# m328.net
KiCad netlist of a schematic drawn in EAGLE
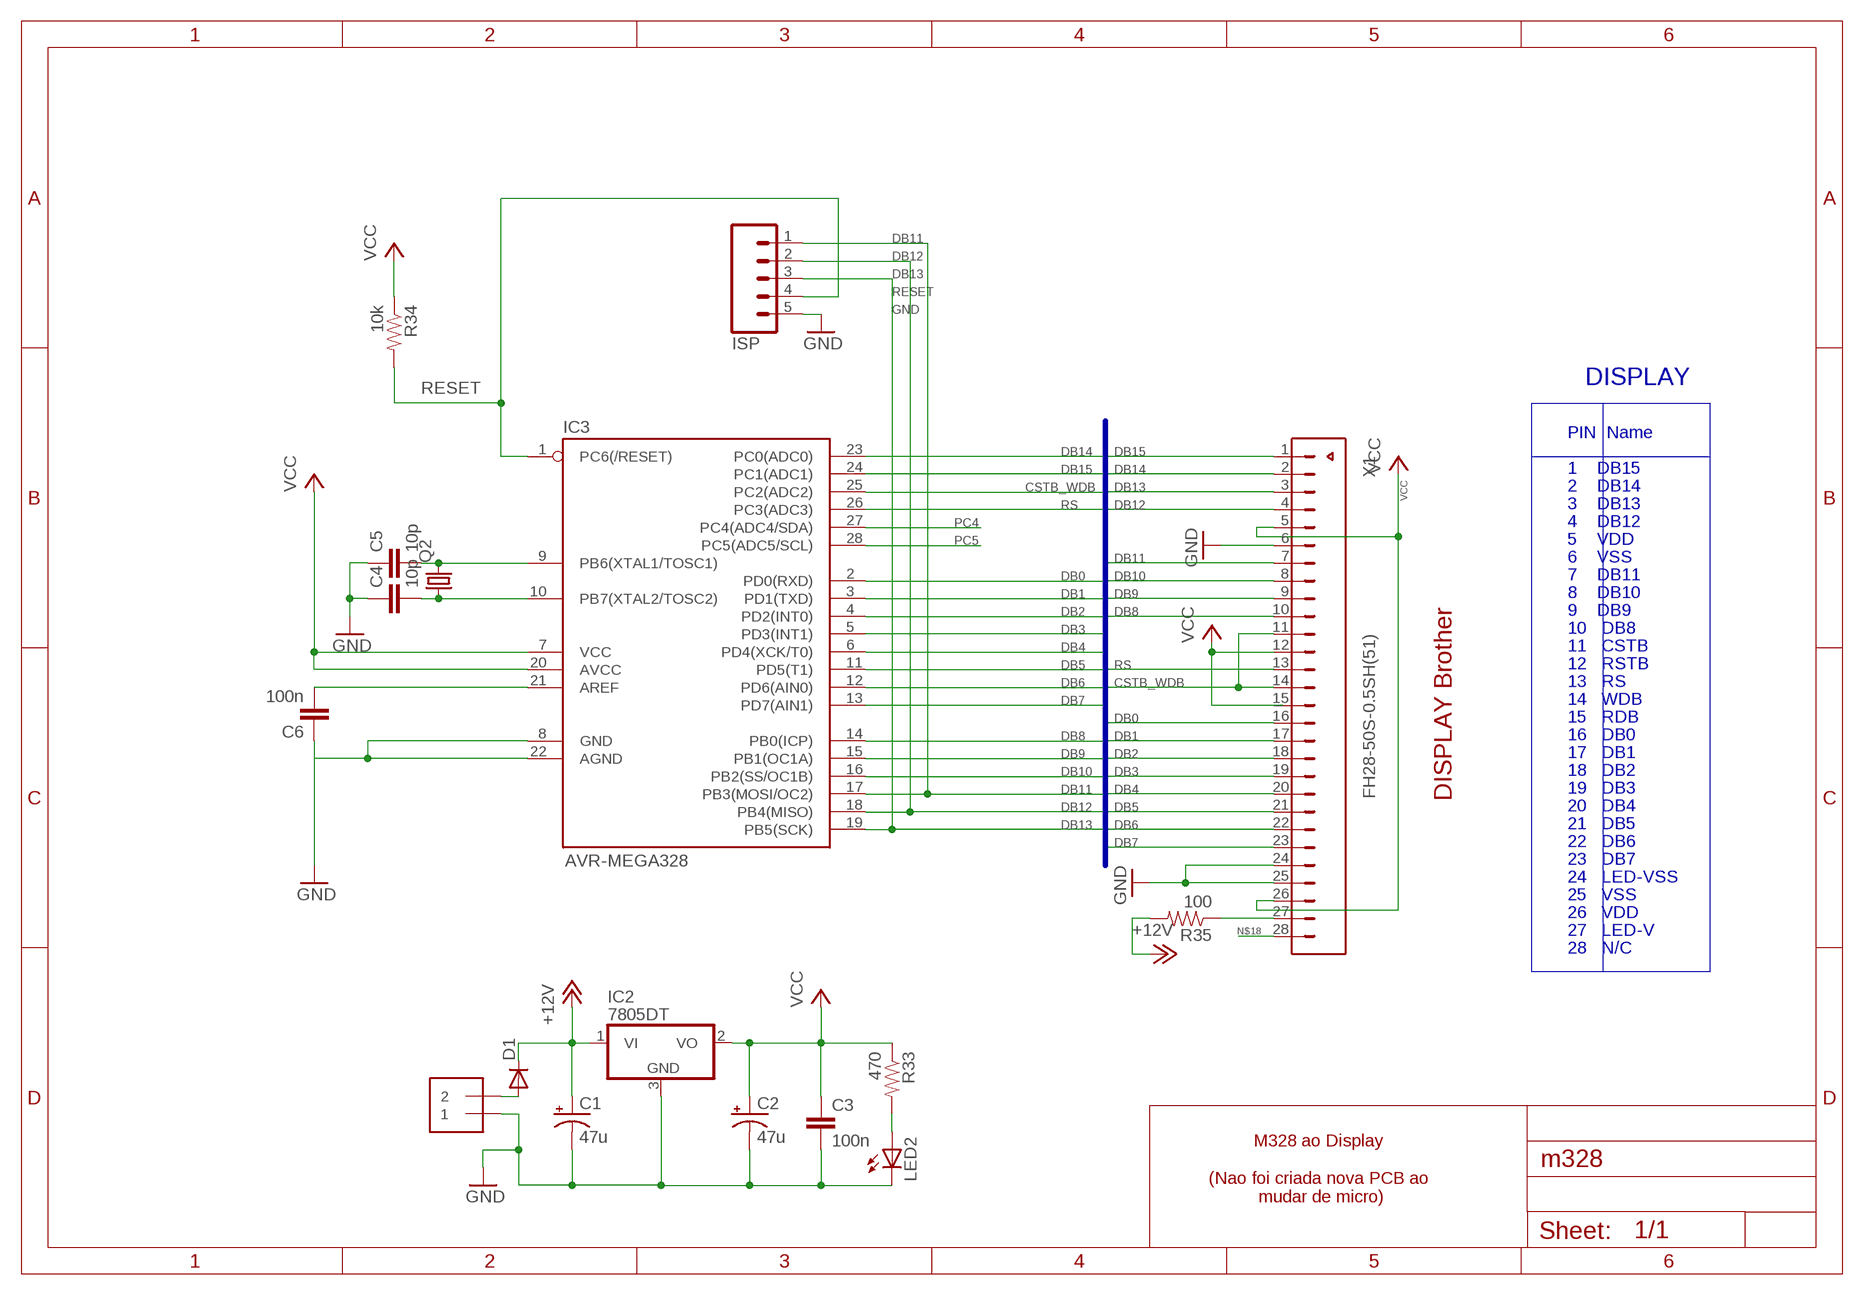
[diagram p0: schematic, sheet 1]

(export (version "E")
  (design (tool "Eeschema 10.0.6"))
  (components
    (comp (ref "C1")
      (value "47u")
      (footprint "eagle-import:EIA3216-KIT")
      (libsource (lib "eagle-import") (part "CAP_POL1206-KIT"))
    )
    (comp (ref "C2")
      (value "47u")
      (footprint "eagle-import:EIA3216-KIT")
      (libsource (lib "eagle-import") (part "CAP_POL1206-KIT"))
    )
    (comp (ref "C3")
      (value "100n")
      (footprint "eagle-import:0805")
      (libsource (lib "eagle-import") (part "CAP0805"))
    )
    (comp (ref "C4")
      (value "10p")
      (footprint "eagle-import:0805")
      (libsource (lib "eagle-import") (part "CAP0805"))
    )
    (comp (ref "C5")
      (value "10p")
      (footprint "eagle-import:0805")
      (libsource (lib "eagle-import") (part "CAP0805"))
    )
    (comp (ref "C6")
      (value "100n")
      (footprint "eagle-import:0805")
      (libsource (lib "eagle-import") (part "CAP0805"))
    )
    (comp (ref "D1")
      (value "DIODESMA-KIT")
      (footprint "eagle-import:SMA-DIODE-KIT")
      (libsource (lib "eagle-import") (part "DIODESMA-KIT"))
    )
    (comp (ref "IC2")
      (value "7805DT")
      (footprint "eagle-import:TO252")
      (libsource (lib "eagle-import") (part "78DT05"))
    )
    (comp (ref "IC3")
      (value "AVR-MEGA328")
      (footprint "eagle-import:DIL28-3")
      (libsource (lib "eagle-import") (part "AVR-MEGA8-PPTH"))
    )
    (comp (ref "ISP")
      (value "M05PTH_LONGPADS")
      (footprint "eagle-import:1X05_LONGPADS")
      (libsource (lib "eagle-import") (part "M05PTH_LONGPADS"))
    )
    (comp (ref "J2")
      (value "1X2-3.5MM")
      (footprint "eagle-import:1X2-3.5MM")
      (libsource (lib "eagle-import") (part "1X2-3.5MM"))
    )
    (comp (ref "LED2")
      (value "LED3MM")
      (footprint "eagle-import:LED3MM")
      (libsource (lib "eagle-import") (part "LED3MM"))
    )
    (comp (ref "Q2")
      (value "CRYSTALHC49UP")
      (footprint "eagle-import:HC49UP")
      (fields (field (name "OC_FARNELL") "unknown"))
      (libsource (lib "eagle-import") (part "CRYSTALHC49UP"))
    )
    (comp (ref "R33")
      (value "470")
      (footprint "eagle-import:0805")
      (libsource (lib "eagle-import") (part "RESISTOR0805-RES"))
    )
    (comp (ref "R34")
      (value "10k")
      (footprint "eagle-import:0805")
      (libsource (lib "eagle-import") (part "RESISTOR0805-RES"))
    )
    (comp (ref "R35")
      (value "100")
      (footprint "eagle-import:0805")
      (libsource (lib "eagle-import") (part "RESISTOR0805-RES"))
    )
    (comp (ref "X1")
      (value "FH28-50S-0.5SH(51)")
      (footprint "eagle-import:FH28-50S-0.5SH(51)")
      (libsource (lib "eagle-import") (part "FH28-50S-0.5SH(51)"))
    )
  )
  (nets
    (net (code "2") (name "+12V") (class "Default")
      (node (ref "C1") (pin "A") (pinfunction "+_A") (pintype "passive"))
      (node (ref "D1") (pin "C") (pinfunction "C_C") (pintype "passive"))
      (node (ref "IC2") (pin "1") (pinfunction "VI_1") (pintype "input"))
      (node (ref "R35") (pin "2") (pinfunction "2_2") (pintype "passive"))
    )
    (net (code "3") (name "/CSTB_WDB") (class "Default")
      (node (ref "IC3") (pin "25") (pinfunction "PC2(ADC2)_25") (pintype "bidirectional"))
      (node (ref "X1") (pin "11") (pinfunction "11_11") (pintype "passive"))
      (node (ref "X1") (pin "14") (pinfunction "14_14") (pintype "passive"))
    )
    (net (code "4") (name "/DB0") (class "Default")
      (node (ref "IC3") (pin "2") (pinfunction "PD0(RXD)_2") (pintype "bidirectional"))
      (node (ref "X1") (pin "16") (pinfunction "16_16") (pintype "passive"))
    )
    (net (code "5") (name "/DB1") (class "Default")
      (node (ref "IC3") (pin "3") (pinfunction "PD1(TXD)_3") (pintype "bidirectional"))
      (node (ref "X1") (pin "17") (pinfunction "17_17") (pintype "passive"))
    )
    (net (code "6") (name "/DB2") (class "Default")
      (node (ref "IC3") (pin "4") (pinfunction "PD2(INT0)_4") (pintype "bidirectional"))
      (node (ref "X1") (pin "18") (pinfunction "18_18") (pintype "passive"))
    )
    (net (code "7") (name "/DB3") (class "Default")
      (node (ref "IC3") (pin "5") (pinfunction "PD3(INT1)_5") (pintype "bidirectional"))
      (node (ref "X1") (pin "19") (pinfunction "19_19") (pintype "passive"))
    )
    (net (code "8") (name "/DB4") (class "Default")
      (node (ref "IC3") (pin "6") (pinfunction "PD4(XCK/T0)_6") (pintype "bidirectional"))
      (node (ref "X1") (pin "20") (pinfunction "20_20") (pintype "passive"))
    )
    (net (code "9") (name "/DB5") (class "Default")
      (node (ref "IC3") (pin "11") (pinfunction "PD5(T1)_11") (pintype "bidirectional"))
      (node (ref "X1") (pin "21") (pinfunction "21_21") (pintype "passive"))
    )
    (net (code "10") (name "/DB6") (class "Default")
      (node (ref "IC3") (pin "12") (pinfunction "PD6(AIN0)_12") (pintype "bidirectional"))
      (node (ref "X1") (pin "22") (pinfunction "22_22") (pintype "passive"))
    )
    (net (code "11") (name "/DB7") (class "Default")
      (node (ref "IC3") (pin "13") (pinfunction "PD7(AIN1)_13") (pintype "bidirectional"))
      (node (ref "X1") (pin "23") (pinfunction "23_23") (pintype "passive"))
    )
    (net (code "12") (name "/DB8") (class "Default")
      (node (ref "IC3") (pin "14") (pinfunction "PB0(ICP)_14") (pintype "bidirectional"))
      (node (ref "X1") (pin "10") (pinfunction "10_10") (pintype "passive"))
    )
    (net (code "13") (name "/DB9") (class "Default")
      (node (ref "IC3") (pin "15") (pinfunction "PB1(OC1A)_15") (pintype "bidirectional"))
      (node (ref "X1") (pin "9") (pinfunction "9_9") (pintype "passive"))
    )
    (net (code "14") (name "/DB10") (class "Default")
      (node (ref "IC3") (pin "16") (pinfunction "PB2(SS/OC1B)_16") (pintype "bidirectional"))
      (node (ref "X1") (pin "8") (pinfunction "8_8") (pintype "passive"))
    )
    (net (code "15") (name "/DB11") (class "Default")
      (node (ref "IC3") (pin "17") (pinfunction "PB3(MOSI/OC2)_17") (pintype "bidirectional"))
      (node (ref "ISP") (pin "1") (pinfunction "1_1") (pintype "passive"))
      (node (ref "X1") (pin "7") (pinfunction "7_7") (pintype "passive"))
    )
    (net (code "16") (name "/DB12") (class "Default")
      (node (ref "IC3") (pin "18") (pinfunction "PB4(MISO)_18") (pintype "bidirectional"))
      (node (ref "ISP") (pin "2") (pinfunction "2_2") (pintype "passive"))
      (node (ref "X1") (pin "4") (pinfunction "4_4") (pintype "passive"))
    )
    (net (code "17") (name "/DB13") (class "Default")
      (node (ref "IC3") (pin "19") (pinfunction "PB5(SCK)_19") (pintype "bidirectional"))
      (node (ref "ISP") (pin "3") (pinfunction "3_3") (pintype "passive"))
      (node (ref "X1") (pin "3") (pinfunction "3_3") (pintype "passive"))
    )
    (net (code "18") (name "/DB14") (class "Default")
      (node (ref "IC3") (pin "23") (pinfunction "PC0(ADC0)_23") (pintype "bidirectional"))
      (node (ref "X1") (pin "2") (pinfunction "2_2") (pintype "passive"))
    )
    (net (code "19") (name "/DB15") (class "Default")
      (node (ref "IC3") (pin "24") (pinfunction "PC1(ADC1)_24") (pintype "bidirectional"))
      (node (ref "X1") (pin "1") (pinfunction "1_1") (pintype "passive"))
    )
    (net (code "20") (name "/N$18") (class "Default")
      (node (ref "X1") (pin "28") (pinfunction "28_28") (pintype "passive"))
    )
    (net (code "21") (name "/PC4") (class "Default")
      (node (ref "IC3") (pin "27") (pinfunction "PC4(ADC4/SDA)_27") (pintype "bidirectional"))
    )
    (net (code "22") (name "/PC5") (class "Default")
      (node (ref "IC3") (pin "28") (pinfunction "PC5(ADC5/SCL)_28") (pintype "bidirectional"))
    )
    (net (code "23") (name "/RESET") (class "Default")
      (node (ref "IC3") (pin "1") (pinfunction "PC6(/RESET)_1") (pintype "bidirectional"))
      (node (ref "ISP") (pin "4") (pinfunction "4_4") (pintype "passive"))
      (node (ref "R34") (pin "2") (pinfunction "2_2") (pintype "passive"))
    )
    (net (code "24") (name "/RS") (class "Default")
      (node (ref "IC3") (pin "26") (pinfunction "PC3(ADC3)_26") (pintype "bidirectional"))
      (node (ref "X1") (pin "13") (pinfunction "13_13") (pintype "passive"))
    )
    (net (code "26") (name "GND") (class "Default")
      (node (ref "C1") (pin "C") (pinfunction "-_C") (pintype "passive"))
      (node (ref "C2") (pin "C") (pinfunction "-_C") (pintype "passive"))
      (node (ref "C3") (pin "2") (pinfunction "2_2") (pintype "passive"))
      (node (ref "C4") (pin "1") (pinfunction "1_1") (pintype "passive"))
      (node (ref "C5") (pin "1") (pinfunction "1_1") (pintype "passive"))
      (node (ref "C6") (pin "1") (pinfunction "1_1") (pintype "passive"))
      (node (ref "IC2") (pin "3") (pinfunction "GND_3") (pintype "passive"))
      (node (ref "IC3") (pin "22") (pinfunction "AGND_22") (pintype "bidirectional"))
      (node (ref "IC3") (pin "8") (pinfunction "GND_8") (pintype "bidirectional"))
      (node (ref "ISP") (pin "5") (pinfunction "5_5") (pintype "passive"))
      (node (ref "J2") (pin "1") (pinfunction "1_1") (pintype "passive"))
      (node (ref "LED2") (pin "K") (pinfunction "C_K") (pintype "passive"))
      (node (ref "X1") (pin "24") (pinfunction "24_24") (pintype "passive"))
      (node (ref "X1") (pin "25") (pinfunction "25_25") (pintype "passive"))
      (node (ref "X1") (pin "6") (pinfunction "6_6") (pintype "passive"))
    )
    (net (code "27") (name "Net-(D1-PadA)") (class "Default")
      (node (ref "D1") (pin "A") (pinfunction "A_A") (pintype "passive"))
      (node (ref "J2") (pin "2") (pinfunction "2_2") (pintype "passive"))
    )
    (net (code "28") (name "Net-(IC3-AREF)") (class "Default")
      (node (ref "C6") (pin "2") (pinfunction "2_2") (pintype "passive"))
      (node (ref "IC3") (pin "21") (pinfunction "AREF_21") (pintype "bidirectional"))
    )
    (net (code "29") (name "Net-(IC3-PB6(XTAL1{slash}TOSC1))") (class "Default")
      (node (ref "C5") (pin "2") (pinfunction "2_2") (pintype "passive"))
      (node (ref "IC3") (pin "9") (pinfunction "PB6(XTAL1/TOSC1)_9") (pintype "bidirectional"))
      (node (ref "Q2") (pin "2") (pinfunction "2_2") (pintype "passive"))
    )
    (net (code "30") (name "Net-(IC3-PB7(XTAL2{slash}TOSC2))") (class "Default")
      (node (ref "C4") (pin "2") (pinfunction "2_2") (pintype "passive"))
      (node (ref "IC3") (pin "10") (pinfunction "PB7(XTAL2/TOSC2)_10") (pintype "bidirectional"))
      (node (ref "Q2") (pin "1") (pinfunction "1_1") (pintype "passive"))
    )
    (net (code "31") (name "Net-(LED2-PadA)") (class "Default")
      (node (ref "LED2") (pin "A") (pinfunction "A_A") (pintype "passive"))
      (node (ref "R33") (pin "2") (pinfunction "2_2") (pintype "passive"))
    )
    (net (code "32") (name "Net-(R35-Pad1)") (class "Default")
      (node (ref "R35") (pin "1") (pinfunction "1_1") (pintype "passive"))
      (node (ref "X1") (pin "27") (pinfunction "27_27") (pintype "passive"))
    )
    (net (code "33") (name "VCC") (class "Default")
      (node (ref "C2") (pin "A") (pinfunction "+_A") (pintype "passive"))
      (node (ref "C3") (pin "1") (pinfunction "1_1") (pintype "passive"))
      (node (ref "IC2") (pin "2") (pinfunction "VO_2") (pintype "passive"))
      (node (ref "IC3") (pin "20") (pinfunction "AVCC_20") (pintype "bidirectional"))
      (node (ref "IC3") (pin "7") (pinfunction "VCC_7") (pintype "bidirectional"))
      (node (ref "R33") (pin "1") (pinfunction "1_1") (pintype "passive"))
      (node (ref "R34") (pin "1") (pinfunction "1_1") (pintype "passive"))
      (node (ref "X1") (pin "12") (pinfunction "12_12") (pintype "passive"))
      (node (ref "X1") (pin "26") (pinfunction "26_26") (pintype "passive"))
      (node (ref "X1") (pin "5") (pinfunction "5_5") (pintype "passive"))
    )
    (net (code "34") (name "unconnected-(X1-Pad15)") (class "Default")
      (node (ref "X1") (pin "15") (pinfunction "15_15") (pintype "passive"))
    )
  )
)
